# HC-SR04_to_I2C_v1.net
KiCad netlist of a schematic drawn in EAGLE
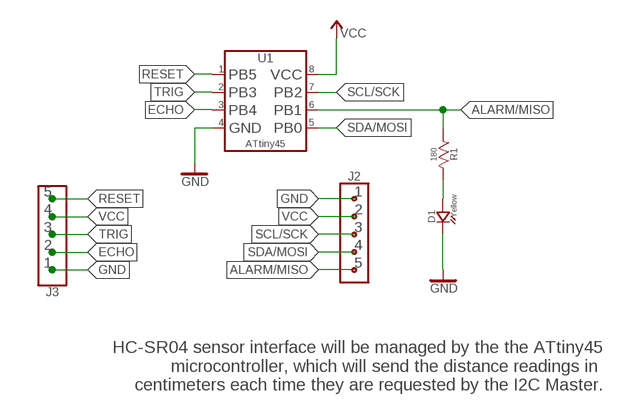
[diagram p0: schematic, sheet 1]

(export (version "E")
  (design (tool "Eeschema 10.0.6"))
  (components
    (comp (ref "D1")
      (value "Yellow")
      (footprint "eagle-import:0805[2012]")
      (libsource (lib "eagle-import") (part "LED_0805[2012]"))
    )
    (comp (ref "J2")
      (value "PIN_HEADER_1X05_0.1\"_STR_G[1]_PTH")
      (footprint "eagle-import:PIN_HEADER_1X05_0.1__STR_G[1]_PTH")
      (libsource (lib "eagle-import") (part "PIN_HEADER_1X05_0.1{dblquote}_STR_G[1]_PTH"))
    )
    (comp (ref "J3")
      (value "PIN_HEADER_1X05_0.1\"_STR_G[1]_PTH")
      (footprint "eagle-import:PIN_HEADER_1X05_0.1__STR_G[1]_PTH")
      (libsource (lib "eagle-import") (part "PIN_HEADER_1X05_0.1{dblquote}_STR_G[1]_PTH"))
    )
    (comp (ref "R1")
      (value "180")
      (footprint "eagle-import:0603[1608]")
      (libsource (lib "eagle-import") (part "RESISTOR_0603[1008]"))
    )
    (comp (ref "U1")
      (value "ATtiny45")
      (footprint "eagle-import:TSSOP_MO-153-AC")
      (libsource (lib "eagle-import") (part "ATTINY25/45/85_TSSOP_MO-153-AC"))
    )
  )
  (nets
    (net (code "1") (name "ALARM{slash}MISO") (class "Default")
      (node (ref "J2") (pin "5") (pinfunction "5_5") (pintype "bidirectional"))
      (node (ref "R1") (pin "1") (pinfunction "P1_1") (pintype "passive"))
      (node (ref "U1") (pin "6") (pinfunction "PB1_6") (pintype "input"))
    )
    (net (code "2") (name "ECHO") (class "Default")
      (node (ref "J3") (pin "2") (pinfunction "2_2") (pintype "bidirectional"))
      (node (ref "U1") (pin "3") (pinfunction "PB4_3") (pintype "bidirectional"))
    )
    (net (code "3") (name "GND") (class "Default")
      (node (ref "D1") (pin "-") (pinfunction "-_-") (pintype "bidirectional"))
      (node (ref "J2") (pin "1") (pinfunction "1_1") (pintype "bidirectional"))
      (node (ref "J3") (pin "1") (pinfunction "1_1") (pintype "bidirectional"))
      (node (ref "U1") (pin "4") (pinfunction "GND_4") (pintype "power_in"))
    )
    (net (code "4") (name "Net-(R1-P2)") (class "Default")
      (node (ref "D1") (pin "+") (pinfunction "+_+") (pintype "bidirectional"))
      (node (ref "R1") (pin "2") (pinfunction "P2_2") (pintype "passive"))
    )
    (net (code "5") (name "RESET") (class "Default")
      (node (ref "J3") (pin "5") (pinfunction "5_5") (pintype "bidirectional"))
      (node (ref "U1") (pin "1") (pinfunction "PB5_1") (pintype "input"))
    )
    (net (code "6") (name "SCL{slash}SCK") (class "Default")
      (node (ref "J2") (pin "3") (pinfunction "3_3") (pintype "bidirectional"))
      (node (ref "U1") (pin "7") (pinfunction "PB2_7") (pintype "input"))
    )
    (net (code "7") (name "SDA{slash}MOSI") (class "Default")
      (node (ref "J2") (pin "4") (pinfunction "4_4") (pintype "bidirectional"))
      (node (ref "U1") (pin "5") (pinfunction "PB0_5") (pintype "input"))
    )
    (net (code "8") (name "TRIG") (class "Default")
      (node (ref "J3") (pin "3") (pinfunction "3_3") (pintype "bidirectional"))
      (node (ref "U1") (pin "2") (pinfunction "PB3_2") (pintype "bidirectional"))
    )
    (net (code "9") (name "VCC") (class "Default")
      (node (ref "J2") (pin "2") (pinfunction "2_2") (pintype "bidirectional"))
      (node (ref "J3") (pin "4") (pinfunction "4_4") (pintype "bidirectional"))
      (node (ref "U1") (pin "8") (pinfunction "VCC_8") (pintype "power_in"))
    )
  )
)
